# Decoder.net
KiCad netlist of a schematic drawn in Altium Designer
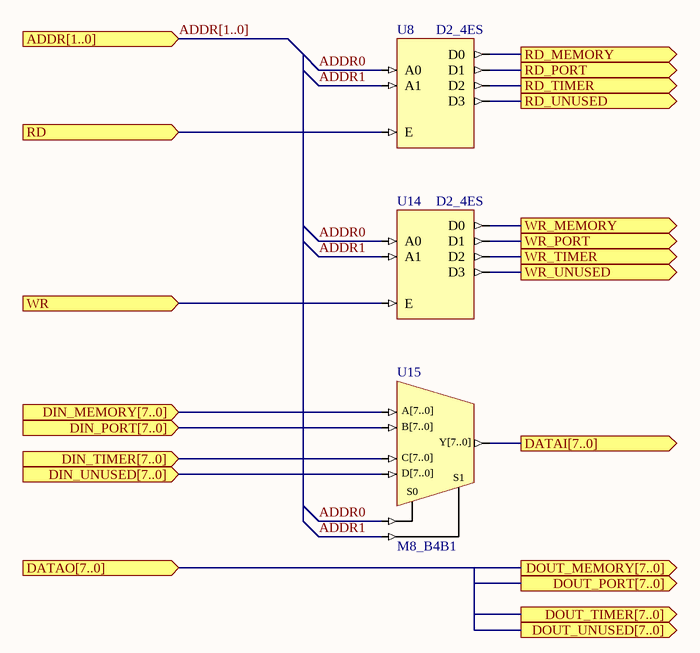
[diagram p0: Decoder.SCHDOC]

(export (version "E")
  (design (tool "Eeschema 10.0.6"))
  (components
    (comp (ref "U8")
      (value "D2_4ES")
      (description "Binary 2- to 4-Bit Decoder with Enable, Single Pin Version")
      (fields (field (name "PUBLISHER") "Altium Limited"))
      (libsource (lib "FPGA Generic") (part "D2_4ES"))
    )
    (comp (ref "U14")
      (value "D2_4ES")
      (description "Binary 2- to 4-Bit Decoder with Enable, Single Pin Version")
      (fields (field (name "PUBLISHER") "Altium Limited"))
      (libsource (lib "FPGA Generic") (part "D2_4ES"))
    )
    (comp (ref "U15")
      (value "M8_B4B1")
      (description "4x8-Bit Bus to 1x8-Bit Bus Multiplexer")
      (fields (field (name "PUBLISHER") "Altium Limited"))
      (libsource (lib "FPGA Generic") (part "M8_B4B1"))
    )
  )
  (nets
    (net (code "73") (name "/ADDR0") (class "Default")
      (node (ref "U14") (pin "A0") (pinfunction "A0_A0") (pintype "input"))
      (node (ref "U15") (pin "S0") (pinfunction "S0_S0") (pintype "input"))
      (node (ref "U8") (pin "A0") (pinfunction "A0_A0") (pintype "input"))
    )
    (net (code "74") (name "/ADDR1") (class "Default")
      (node (ref "U14") (pin "A1") (pinfunction "A1_A1") (pintype "input"))
      (node (ref "U15") (pin "S1") (pinfunction "S1_S1") (pintype "input"))
      (node (ref "U8") (pin "A1") (pinfunction "A1_A1") (pintype "input"))
    )
    (net (code "76") (name "/DATAI[7..0]") (class "Default")
      (node (ref "U15") (pin "Y[7..0]") (pinfunction "Y[7..0]_Y[7..0]") (pintype "output"))
    )
    (net (code "78") (name "/DIN_MEMORY[7..0]") (class "Default")
      (node (ref "U15") (pin "A[7..0]") (pinfunction "A[7..0]_A[7..0]") (pintype "input"))
    )
    (net (code "79") (name "/DIN_PORT[7..0]") (class "Default")
      (node (ref "U15") (pin "B[7..0]") (pinfunction "B[7..0]_B[7..0]") (pintype "input"))
    )
    (net (code "80") (name "/DIN_TIMER[7..0]") (class "Default")
      (node (ref "U15") (pin "C[7..0]") (pinfunction "C[7..0]_C[7..0]") (pintype "input"))
    )
    (net (code "81") (name "/DIN_UNUSED[7..0]") (class "Default")
      (node (ref "U15") (pin "D[7..0]") (pinfunction "D[7..0]_D[7..0]") (pintype "input"))
    )
    (net (code "85") (name "/RD") (class "Default")
      (node (ref "U8") (pin "E") (pinfunction "E_E") (pintype "input"))
    )
    (net (code "86") (name "/RD_MEMORY") (class "Default")
      (node (ref "U8") (pin "D0") (pinfunction "D0_D0") (pintype "output"))
    )
    (net (code "87") (name "/RD_PORT") (class "Default")
      (node (ref "U8") (pin "D1") (pinfunction "D1_D1") (pintype "output"))
    )
    (net (code "88") (name "/RD_TIMER") (class "Default")
      (node (ref "U8") (pin "D2") (pinfunction "D2_D2") (pintype "output"))
    )
    (net (code "89") (name "/RD_UNUSED") (class "Default")
      (node (ref "U8") (pin "D3") (pinfunction "D3_D3") (pintype "output"))
    )
    (net (code "90") (name "/WR") (class "Default")
      (node (ref "U14") (pin "E") (pinfunction "E_E") (pintype "input"))
    )
    (net (code "91") (name "/WR_MEMORY") (class "Default")
      (node (ref "U14") (pin "D0") (pinfunction "D0_D0") (pintype "output"))
    )
    (net (code "92") (name "/WR_PORT") (class "Default")
      (node (ref "U14") (pin "D1") (pinfunction "D1_D1") (pintype "output"))
    )
    (net (code "93") (name "/WR_TIMER") (class "Default")
      (node (ref "U14") (pin "D2") (pinfunction "D2_D2") (pintype "output"))
    )
    (net (code "94") (name "/WR_UNUSED") (class "Default")
      (node (ref "U14") (pin "D3") (pinfunction "D3_D3") (pintype "output"))
    )
  )
)
